# MCDU_R.net
KiCad netlist of a schematic drawn in EAGLE
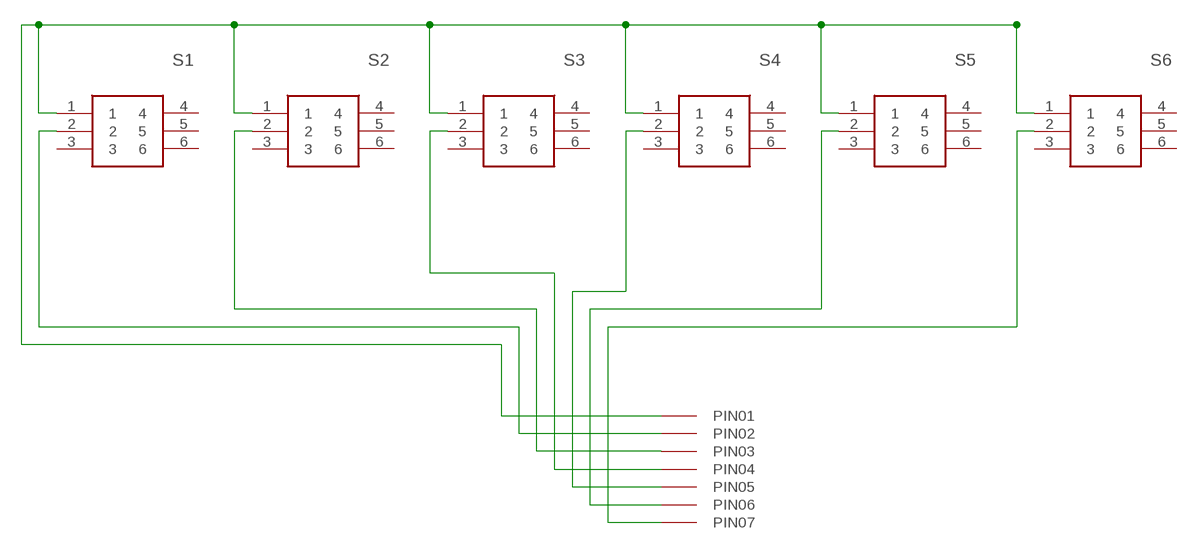
[diagram p0: schematic, sheet 1]

(export (version "E")
  (design (tool "Eeschema 10.0.6"))
  (components
    (comp (ref "S1")
      (value "PVA2EEH1_1.7NV2")
      (footprint "eagle-import:PVA2")
      (fields (field (name "ARROW_PART_NUMBER") "PVA2EEH1 1.7NV2"))
      (libsource (lib "eagle-import") (part "PVA2EEH1_1.7NV2"))
    )
    (comp (ref "S2")
      (value "PVA2EEH1_1.7NV2")
      (footprint "eagle-import:PVA2")
      (fields (field (name "ARROW_PART_NUMBER") "PVA2EEH1 1.7NV2"))
      (libsource (lib "eagle-import") (part "PVA2EEH1_1.7NV2"))
    )
    (comp (ref "S3")
      (value "PVA2EEH1_1.7NV2")
      (footprint "eagle-import:PVA2")
      (fields (field (name "ARROW_PART_NUMBER") "PVA2EEH1 1.7NV2"))
      (libsource (lib "eagle-import") (part "PVA2EEH1_1.7NV2"))
    )
    (comp (ref "S4")
      (value "PVA2EEH1_1.7NV2")
      (footprint "eagle-import:PVA2")
      (fields (field (name "ARROW_PART_NUMBER") "PVA2EEH1 1.7NV2"))
      (libsource (lib "eagle-import") (part "PVA2EEH1_1.7NV2"))
    )
    (comp (ref "S5")
      (value "PVA2EEH1_1.7NV2")
      (footprint "eagle-import:PVA2")
      (fields (field (name "ARROW_PART_NUMBER") "PVA2EEH1 1.7NV2"))
      (libsource (lib "eagle-import") (part "PVA2EEH1_1.7NV2"))
    )
    (comp (ref "S6")
      (value "PVA2EEH1_1.7NV2")
      (footprint "eagle-import:PVA2")
      (fields (field (name "ARROW_PART_NUMBER") "PVA2EEH1 1.7NV2"))
      (libsource (lib "eagle-import") (part "PVA2EEH1_1.7NV2"))
    )
    (comp (ref "U$1")
      (value "07PINOS")
      (footprint "eagle-import:07PINOS")
      (libsource (lib "eagle-import") (part "07PINOS"))
    )
  )
  (nets
    (net (code "1") (name "Net-(S1-Pad1)") (class "Default")
      (node (ref "S1") (pin "1") (pinfunction "1_1") (pintype "bidirectional"))
      (node (ref "S2") (pin "1") (pinfunction "1_1") (pintype "bidirectional"))
      (node (ref "S3") (pin "1") (pinfunction "1_1") (pintype "bidirectional"))
      (node (ref "S4") (pin "1") (pinfunction "1_1") (pintype "bidirectional"))
      (node (ref "S5") (pin "1") (pinfunction "1_1") (pintype "bidirectional"))
      (node (ref "S6") (pin "1") (pinfunction "1_1") (pintype "bidirectional"))
      (node (ref "U$1") (pin "PIN01") (pinfunction "PIN01_PIN01") (pintype "bidirectional"))
    )
    (net (code "2") (name "Net-(S1-Pad2)") (class "Default")
      (node (ref "S1") (pin "2") (pinfunction "2_2") (pintype "bidirectional"))
      (node (ref "U$1") (pin "PIN02") (pinfunction "PIN02_PIN02") (pintype "bidirectional"))
    )
    (net (code "3") (name "Net-(S2-Pad2)") (class "Default")
      (node (ref "S2") (pin "2") (pinfunction "2_2") (pintype "bidirectional"))
      (node (ref "U$1") (pin "PIN03") (pinfunction "PIN03_PIN03") (pintype "bidirectional"))
    )
    (net (code "4") (name "Net-(S3-Pad2)") (class "Default")
      (node (ref "S3") (pin "2") (pinfunction "2_2") (pintype "bidirectional"))
      (node (ref "U$1") (pin "PIN04") (pinfunction "PIN04_PIN04") (pintype "bidirectional"))
    )
    (net (code "5") (name "Net-(S4-Pad2)") (class "Default")
      (node (ref "S4") (pin "2") (pinfunction "2_2") (pintype "bidirectional"))
      (node (ref "U$1") (pin "PIN05") (pinfunction "PIN05_PIN05") (pintype "bidirectional"))
    )
    (net (code "6") (name "Net-(S5-Pad2)") (class "Default")
      (node (ref "S5") (pin "2") (pinfunction "2_2") (pintype "bidirectional"))
      (node (ref "U$1") (pin "PIN06") (pinfunction "PIN06_PIN06") (pintype "bidirectional"))
    )
    (net (code "7") (name "Net-(S6-Pad2)") (class "Default")
      (node (ref "S6") (pin "2") (pinfunction "2_2") (pintype "bidirectional"))
      (node (ref "U$1") (pin "PIN07") (pinfunction "PIN07_PIN07") (pintype "bidirectional"))
    )
    (net (code "8") (name "unconnected-(S1-Pad3)") (class "Default")
      (node (ref "S1") (pin "3") (pinfunction "3_3") (pintype "bidirectional"))
    )
    (net (code "9") (name "unconnected-(S1-Pad4)") (class "Default")
      (node (ref "S1") (pin "4") (pinfunction "4_4") (pintype "bidirectional"))
    )
    (net (code "10") (name "unconnected-(S1-Pad5)") (class "Default")
      (node (ref "S1") (pin "5") (pinfunction "5_5") (pintype "bidirectional"))
    )
    (net (code "11") (name "unconnected-(S1-Pad6)") (class "Default")
      (node (ref "S1") (pin "6") (pinfunction "6_6") (pintype "bidirectional"))
    )
    (net (code "12") (name "unconnected-(S2-Pad3)") (class "Default")
      (node (ref "S2") (pin "3") (pinfunction "3_3") (pintype "bidirectional"))
    )
    (net (code "13") (name "unconnected-(S2-Pad4)") (class "Default")
      (node (ref "S2") (pin "4") (pinfunction "4_4") (pintype "bidirectional"))
    )
    (net (code "14") (name "unconnected-(S2-Pad5)") (class "Default")
      (node (ref "S2") (pin "5") (pinfunction "5_5") (pintype "bidirectional"))
    )
    (net (code "15") (name "unconnected-(S2-Pad6)") (class "Default")
      (node (ref "S2") (pin "6") (pinfunction "6_6") (pintype "bidirectional"))
    )
    (net (code "16") (name "unconnected-(S3-Pad3)") (class "Default")
      (node (ref "S3") (pin "3") (pinfunction "3_3") (pintype "bidirectional"))
    )
    (net (code "17") (name "unconnected-(S3-Pad4)") (class "Default")
      (node (ref "S3") (pin "4") (pinfunction "4_4") (pintype "bidirectional"))
    )
    (net (code "18") (name "unconnected-(S3-Pad5)") (class "Default")
      (node (ref "S3") (pin "5") (pinfunction "5_5") (pintype "bidirectional"))
    )
    (net (code "19") (name "unconnected-(S3-Pad6)") (class "Default")
      (node (ref "S3") (pin "6") (pinfunction "6_6") (pintype "bidirectional"))
    )
    (net (code "20") (name "unconnected-(S4-Pad3)") (class "Default")
      (node (ref "S4") (pin "3") (pinfunction "3_3") (pintype "bidirectional"))
    )
    (net (code "21") (name "unconnected-(S4-Pad4)") (class "Default")
      (node (ref "S4") (pin "4") (pinfunction "4_4") (pintype "bidirectional"))
    )
    (net (code "22") (name "unconnected-(S4-Pad5)") (class "Default")
      (node (ref "S4") (pin "5") (pinfunction "5_5") (pintype "bidirectional"))
    )
    (net (code "23") (name "unconnected-(S4-Pad6)") (class "Default")
      (node (ref "S4") (pin "6") (pinfunction "6_6") (pintype "bidirectional"))
    )
    (net (code "24") (name "unconnected-(S5-Pad3)") (class "Default")
      (node (ref "S5") (pin "3") (pinfunction "3_3") (pintype "bidirectional"))
    )
    (net (code "25") (name "unconnected-(S5-Pad4)") (class "Default")
      (node (ref "S5") (pin "4") (pinfunction "4_4") (pintype "bidirectional"))
    )
    (net (code "26") (name "unconnected-(S5-Pad5)") (class "Default")
      (node (ref "S5") (pin "5") (pinfunction "5_5") (pintype "bidirectional"))
    )
    (net (code "27") (name "unconnected-(S5-Pad6)") (class "Default")
      (node (ref "S5") (pin "6") (pinfunction "6_6") (pintype "bidirectional"))
    )
    (net (code "28") (name "unconnected-(S6-Pad3)") (class "Default")
      (node (ref "S6") (pin "3") (pinfunction "3_3") (pintype "bidirectional"))
    )
    (net (code "29") (name "unconnected-(S6-Pad4)") (class "Default")
      (node (ref "S6") (pin "4") (pinfunction "4_4") (pintype "bidirectional"))
    )
    (net (code "30") (name "unconnected-(S6-Pad5)") (class "Default")
      (node (ref "S6") (pin "5") (pinfunction "5_5") (pintype "bidirectional"))
    )
    (net (code "31") (name "unconnected-(S6-Pad6)") (class "Default")
      (node (ref "S6") (pin "6") (pinfunction "6_6") (pintype "bidirectional"))
    )
  )
)
